# rpiPower_Hat.net
KiCad netlist of a schematic drawn in EAGLE
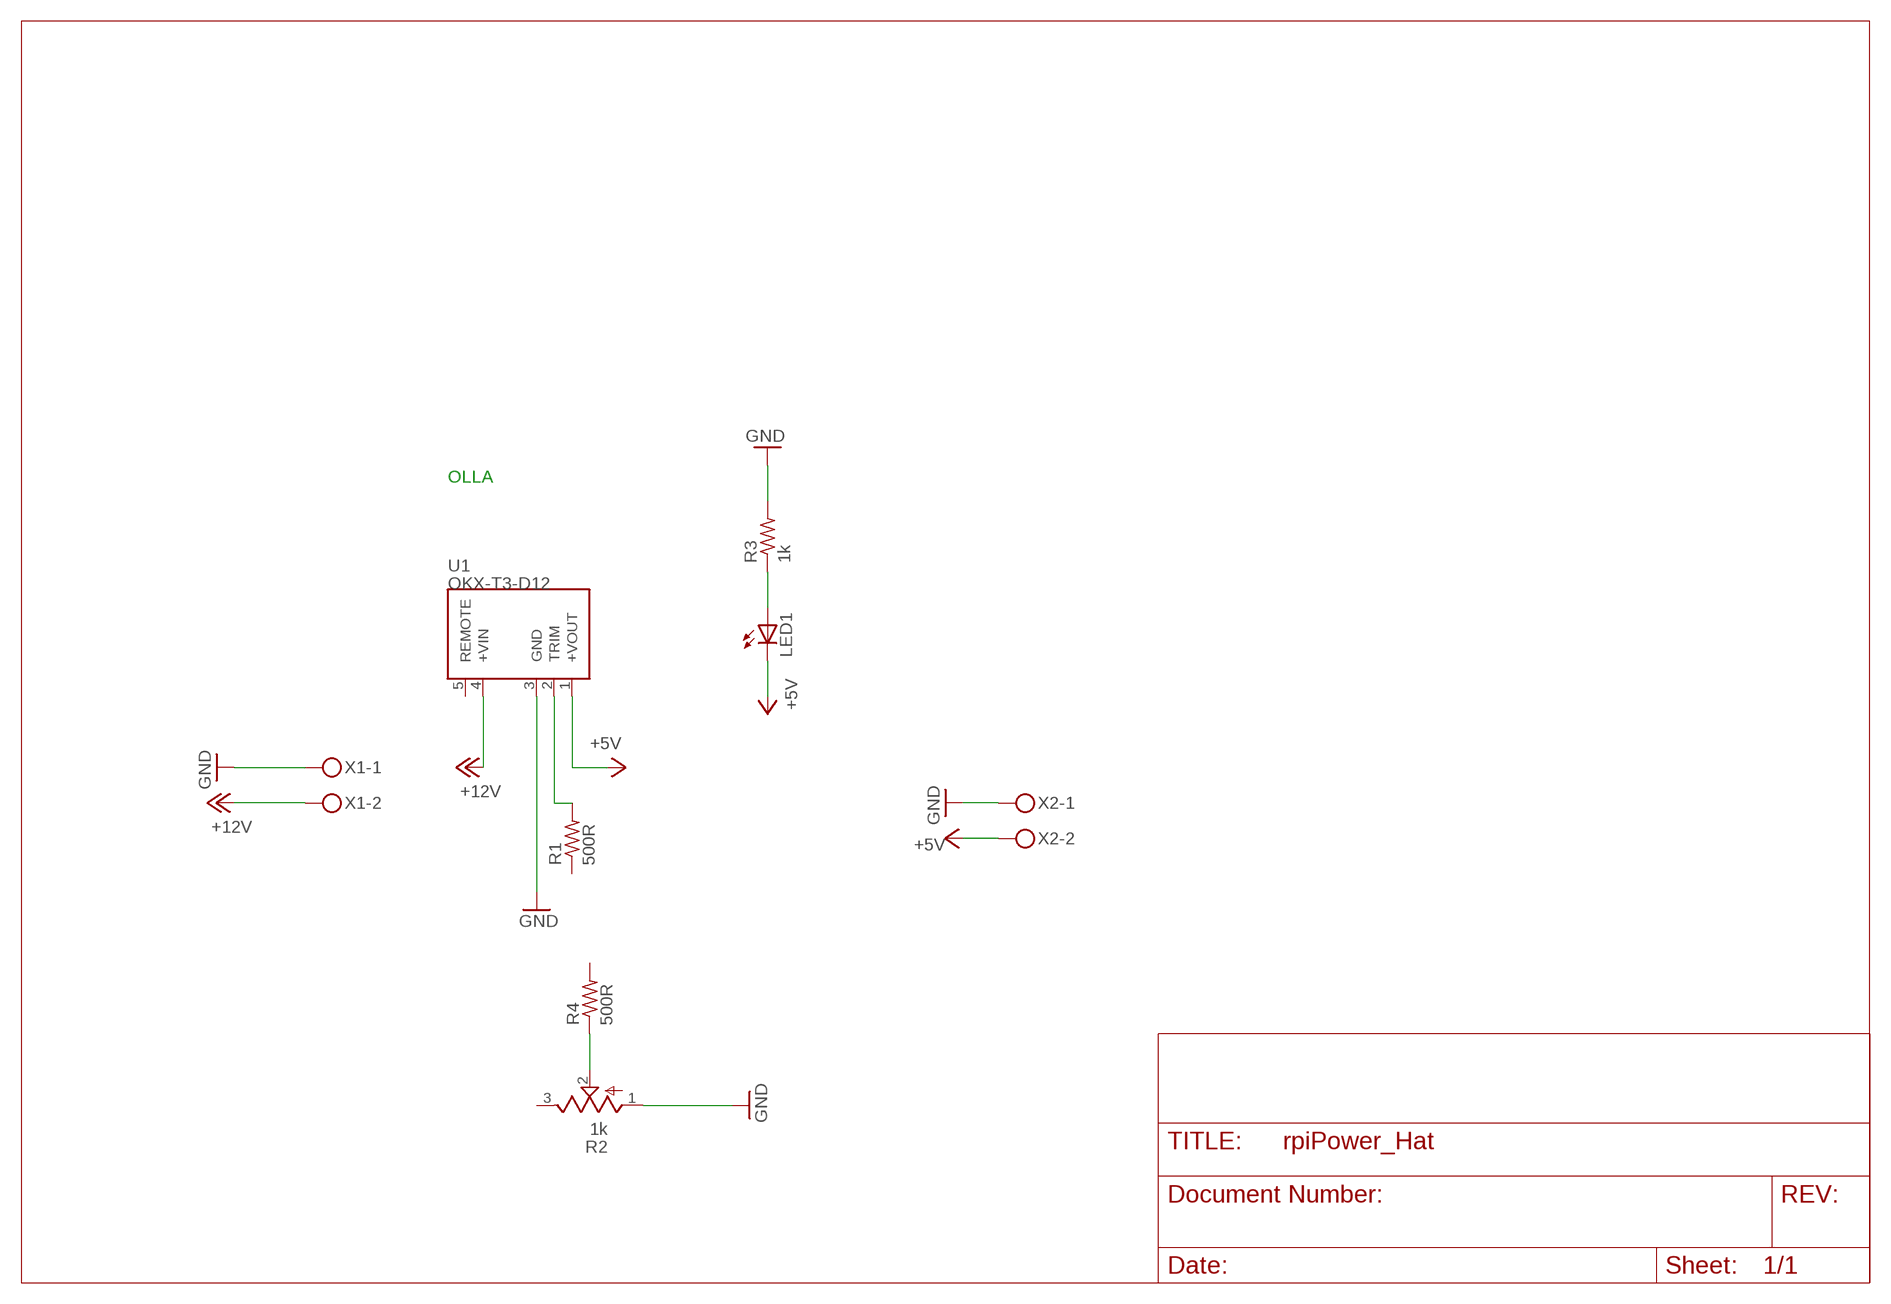
[diagram p0: schematic, sheet 1]

(export (version "E")
  (design (tool "Eeschema 10.0.6"))
  (components
    (comp (ref "LED1")
      (value "LEDCHIP-LED0603")
      (footprint "eagle-import:CHIP-LED0603")
      (libsource (lib "eagle-import") (part "LEDCHIP-LED0603"))
    )
    (comp (ref "R1")
      (value "500R")
      (footprint "eagle-import:R0603")
      (libsource (lib "eagle-import") (part "R-US_R0603"))
    )
    (comp (ref "R2")
      (value "1k")
      (footprint "eagle-import:RTRIM3296W")
      (libsource (lib "eagle-import") (part "POT-3296W"))
    )
    (comp (ref "R3")
      (value "1k")
      (footprint "eagle-import:R0603")
      (libsource (lib "eagle-import") (part "R-US_R0603"))
    )
    (comp (ref "R4")
      (value "500R")
      (footprint "eagle-import:R0603")
      (libsource (lib "eagle-import") (part "R-US_R0603"))
    )
    (comp (ref "U1")
      (value "OKX-T3-D12")
      (footprint "eagle-import:OKX-T3-D12")
      (libsource (lib "eagle-import") (part "OKX-T3-D12"))
    )
    (comp (ref "X1")
      (value "MKDSN1,5/2-5,08")
      (footprint "eagle-import:MKDSN1,5_2-5,08")
      (libsource (lib "eagle-import") (part "MKDSN1,5/2-5,08"))
    )
    (comp (ref "X2")
      (value "MKDSN1,5/2-5,08")
      (footprint "eagle-import:MKDSN1,5_2-5,08")
      (libsource (lib "eagle-import") (part "MKDSN1,5/2-5,08"))
    )
  )
  (nets
    (net (code "1") (name "+5V") (class "Default")
      (node (ref "LED1") (pin "C") (pinfunction "C_C") (pintype "passive"))
      (node (ref "U1") (pin "1") (pinfunction "+VOUT_1") (pintype "bidirectional"))
      (node (ref "X2") (pin "2") (pinfunction "KL_2") (pintype "passive"))
    )
    (net (code "2") (name "+12V") (class "Default")
      (node (ref "U1") (pin "4") (pinfunction "+VIN_4") (pintype "bidirectional"))
      (node (ref "X1") (pin "2") (pinfunction "KL_2") (pintype "passive"))
    )
    (net (code "3") (name "GND") (class "Default")
      (node (ref "R2") (pin "1") (pinfunction "A_1") (pintype "passive"))
      (node (ref "R3") (pin "2") (pinfunction "2_2") (pintype "passive"))
      (node (ref "U1") (pin "3") (pinfunction "GND_3") (pintype "bidirectional"))
      (node (ref "X1") (pin "1") (pinfunction "KL_1") (pintype "passive"))
      (node (ref "X2") (pin "1") (pinfunction "KL_1") (pintype "passive"))
    )
    (net (code "4") (name "Net-(LED1-PadA)") (class "Default")
      (node (ref "LED1") (pin "A") (pinfunction "A_A") (pintype "passive"))
      (node (ref "R3") (pin "1") (pinfunction "1_1") (pintype "passive"))
    )
    (net (code "5") (name "Net-(R2-S)") (class "Default")
      (node (ref "R2") (pin "2") (pinfunction "S_2") (pintype "passive"))
      (node (ref "R4") (pin "1") (pinfunction "1_1") (pintype "passive"))
    )
    (net (code "6") (name "Net-(U1-TRIM)") (class "Default")
      (node (ref "R1") (pin "2") (pinfunction "2_2") (pintype "passive"))
      (node (ref "U1") (pin "2") (pinfunction "TRIM_2") (pintype "bidirectional"))
    )
    (net (code "7") (name "unconnected-(R1-Pad1)") (class "Default")
      (node (ref "R1") (pin "1") (pinfunction "1_1") (pintype "passive"))
    )
    (net (code "8") (name "unconnected-(R2-E-Pad3)") (class "Default")
      (node (ref "R2") (pin "3") (pinfunction "E_3") (pintype "passive"))
    )
    (net (code "9") (name "unconnected-(R4-Pad2)") (class "Default")
      (node (ref "R4") (pin "2") (pinfunction "2_2") (pintype "passive"))
    )
    (net (code "10") (name "unconnected-(U1-REMOTE-Pad5)") (class "Default")
      (node (ref "U1") (pin "5") (pinfunction "REMOTE_5") (pintype "bidirectional"))
    )
  )
)
